# QCopterFC_CAMSPI_Sch.net
KiCad netlist of a schematic drawn in Altium Designer
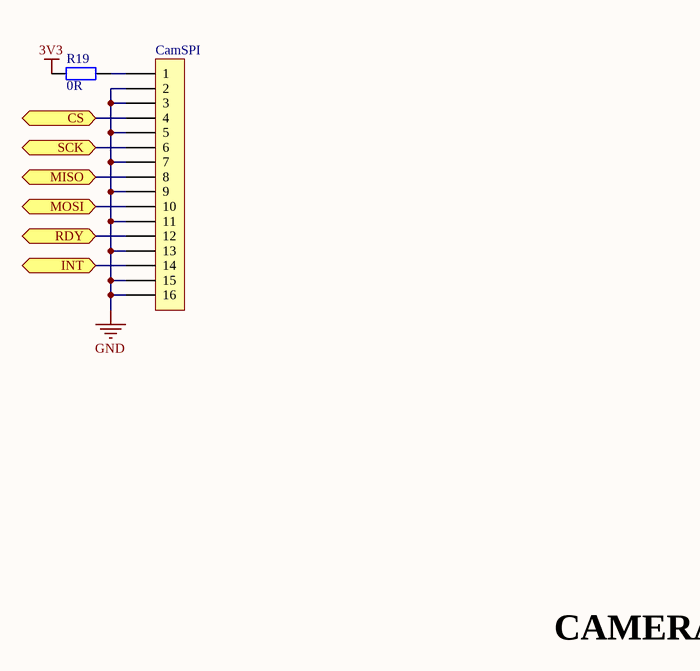
[diagram p0: QCopterFC_CAMSPI_Sch.SchDoc]

(export (version "E")
  (design (tool "Eeschema 10.0.6"))
  (components
    (comp (ref "CamSPI")
      (value "FFC_0.5_16")
      (footprint "PCB_Connector:FFC_0.5_16")
      (description "FFC")
      (libsource (lib "SCH_Connector") (part "FFC_0.5_16"))
    )
    (comp (ref "R19")
      (value "0R")
      (footprint "PCB_Passive:RES_0603")
      (description "Resistor")
      (fields (field (name "Comment") "Res_0603"))
      (libsource (lib "SCH_Passive") (part "Res_0603"))
    )
  )
  (nets
    (net (code "1") (name "/CS") (class "Default")
      (node (ref "CamSPI") (pin "4") (pinfunction "4_4") (pintype "passive"))
    )
    (net (code "2") (name "/INT") (class "Default")
      (node (ref "CamSPI") (pin "14") (pinfunction "14_14") (pintype "passive"))
    )
    (net (code "3") (name "/MISO") (class "Default")
      (node (ref "CamSPI") (pin "8") (pinfunction "8_8") (pintype "passive"))
    )
    (net (code "4") (name "/MOSI") (class "Default")
      (node (ref "CamSPI") (pin "10") (pinfunction "10_10") (pintype "passive"))
    )
    (net (code "5") (name "/RDY") (class "Default")
      (node (ref "CamSPI") (pin "12") (pinfunction "12_12") (pintype "passive"))
    )
    (net (code "6") (name "/SCK") (class "Default")
      (node (ref "CamSPI") (pin "6") (pinfunction "6_6") (pintype "passive"))
    )
    (net (code "7") (name "3V3") (class "Default")
      (node (ref "R19") (pin "1") (pinfunction "1_1") (pintype "passive"))
    )
    (net (code "8") (name "GND") (class "Default")
      (node (ref "CamSPI") (pin "11") (pinfunction "11_11") (pintype "passive"))
      (node (ref "CamSPI") (pin "13") (pinfunction "13_13") (pintype "passive"))
      (node (ref "CamSPI") (pin "15") (pinfunction "15_15") (pintype "passive"))
      (node (ref "CamSPI") (pin "16") (pinfunction "16_16") (pintype "passive"))
      (node (ref "CamSPI") (pin "2") (pinfunction "2_2") (pintype "passive"))
      (node (ref "CamSPI") (pin "3") (pinfunction "3_3") (pintype "passive"))
      (node (ref "CamSPI") (pin "5") (pinfunction "5_5") (pintype "passive"))
      (node (ref "CamSPI") (pin "7") (pinfunction "7_7") (pintype "passive"))
      (node (ref "CamSPI") (pin "9") (pinfunction "9_9") (pintype "passive"))
    )
    (net (code "9") (name "Net-(CamSPI-Pad1)") (class "Default")
      (node (ref "CamSPI") (pin "1") (pinfunction "1_1") (pintype "passive"))
      (node (ref "R19") (pin "2") (pinfunction "2_2") (pintype "passive"))
    )
  )
)
